# electromyography_3_channels.net
KiCad netlist of a schematic drawn in EAGLE
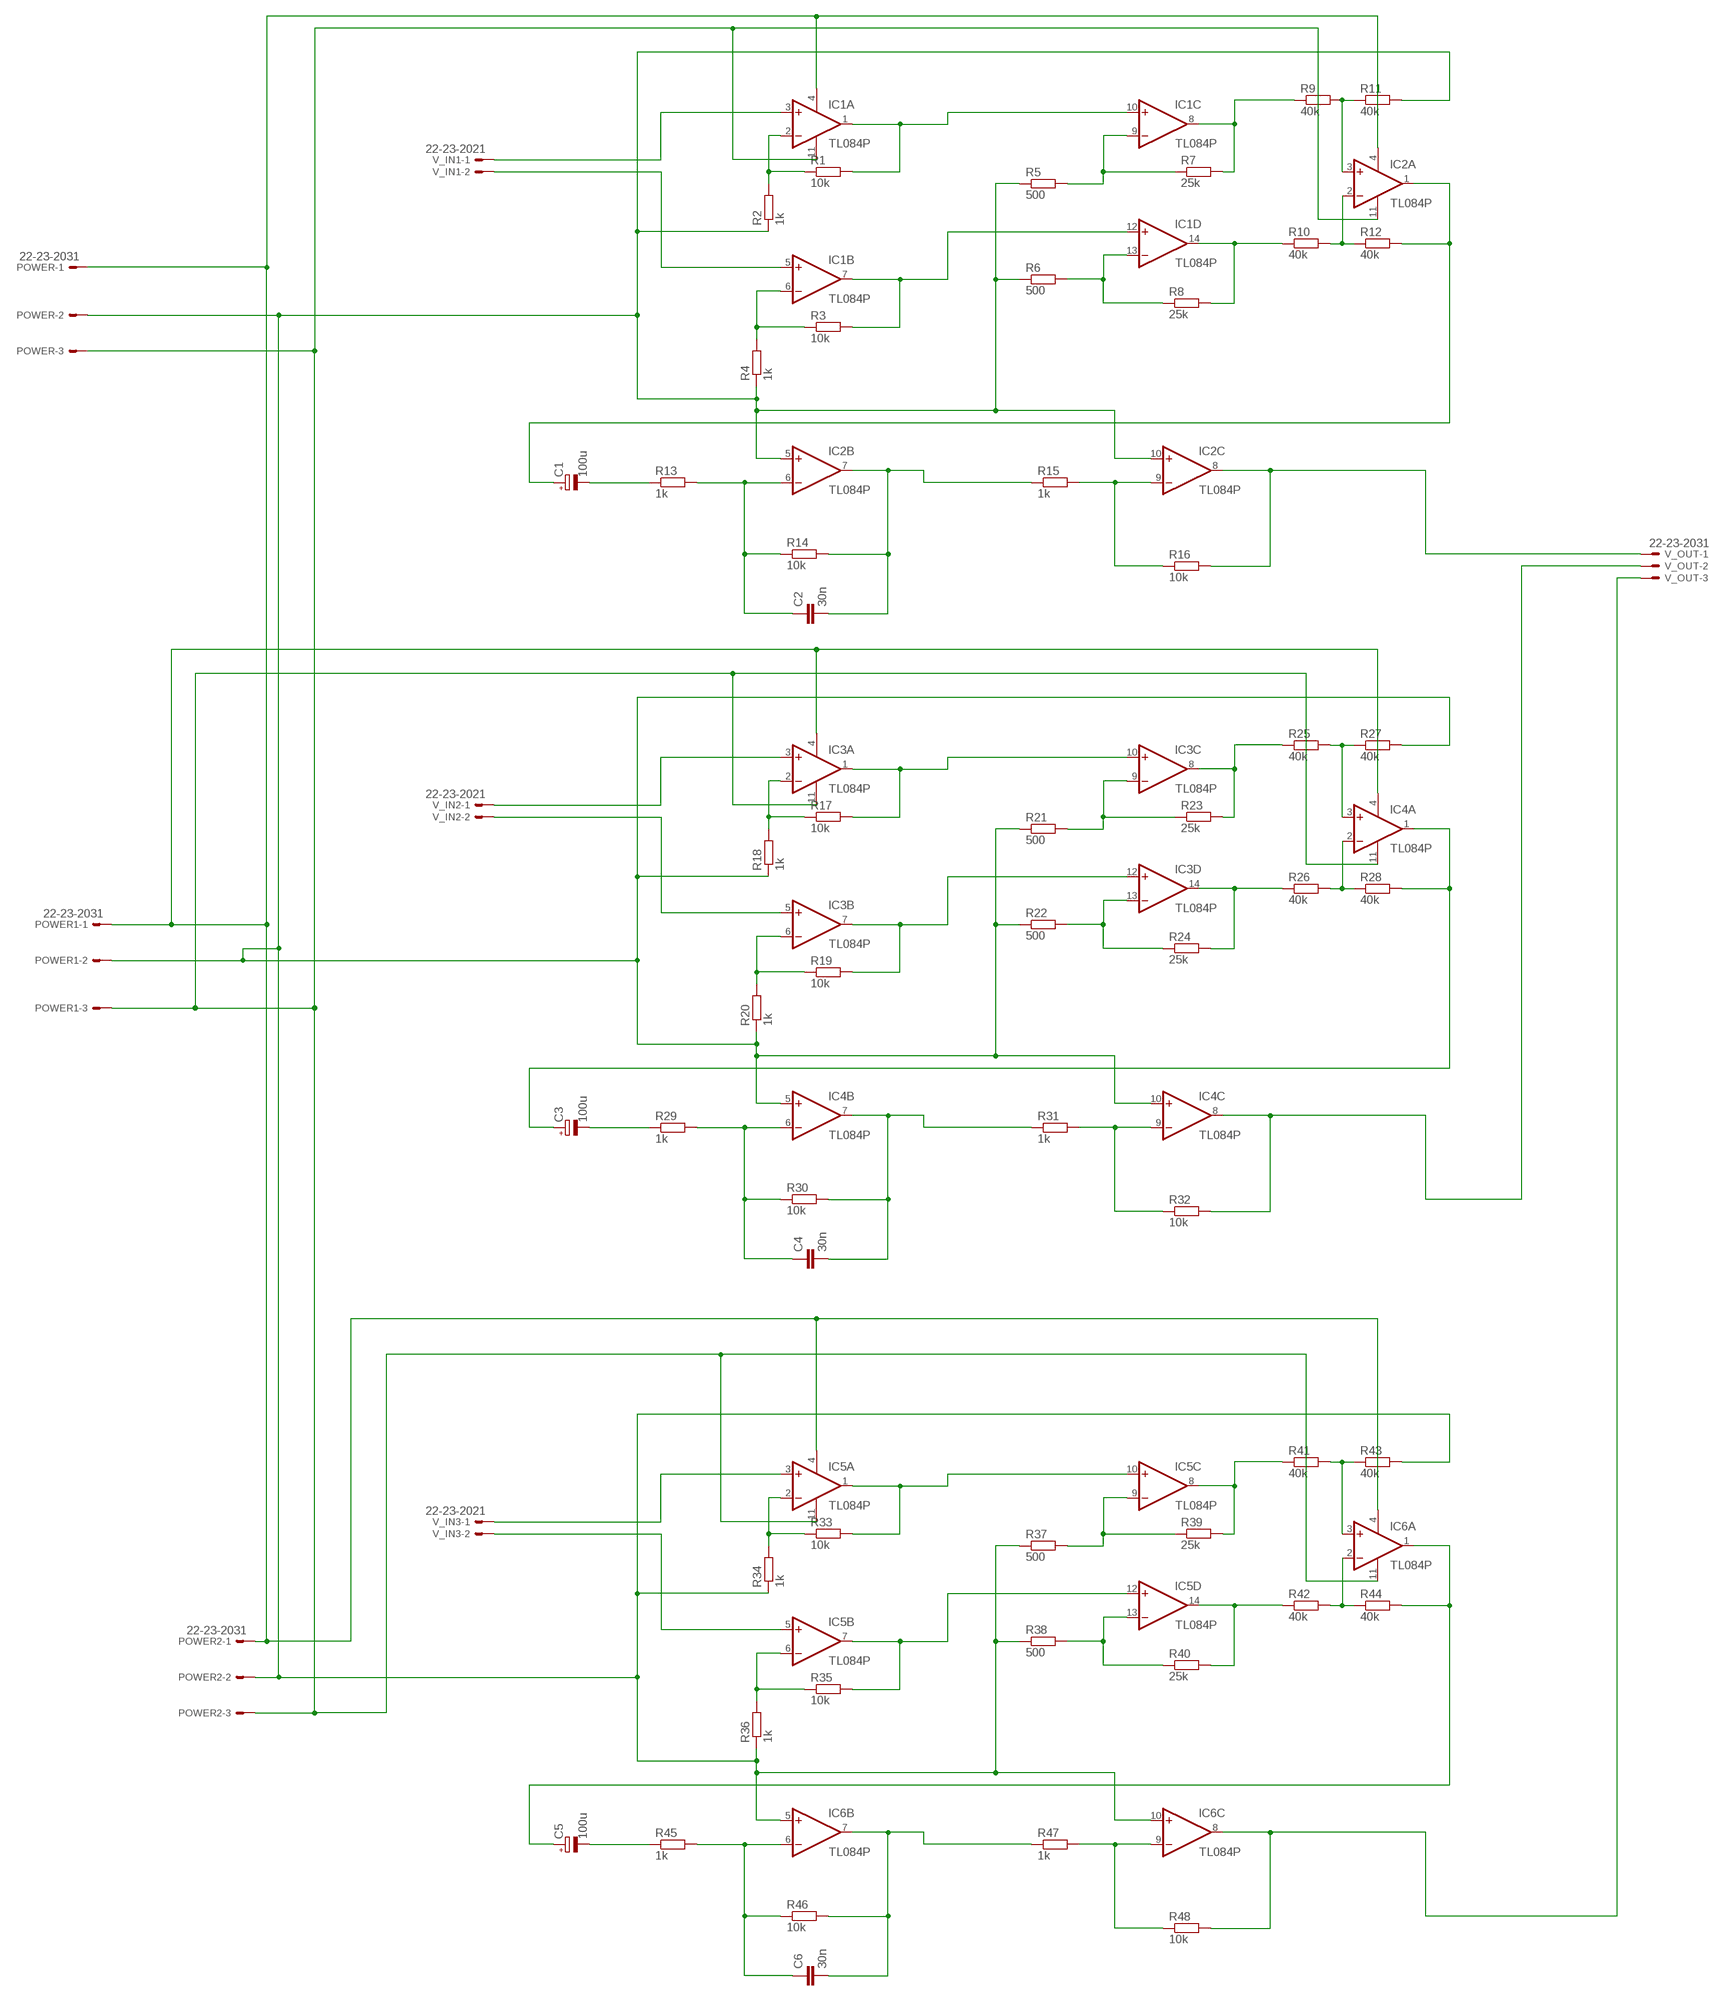
[diagram p0: schematic, sheet 1]

(export (version "E")
  (design (tool "Eeschema 10.0.6"))
  (components
    (comp (ref "C1")
      (value "100u")
      (footprint "eagle-import:E3,5-8")
      (libsource (lib "eagle-import") (part "CPOL-EUE3.5-8"))
    )
    (comp (ref "C2")
      (value "30n")
      (footprint "eagle-import:C050-024X044")
      (libsource (lib "eagle-import") (part "C-EU050-024X044"))
    )
    (comp (ref "C3")
      (value "100u")
      (footprint "eagle-import:E3,5-8")
      (libsource (lib "eagle-import") (part "CPOL-EUE3.5-8"))
    )
    (comp (ref "C4")
      (value "30n")
      (footprint "eagle-import:C050-024X044")
      (libsource (lib "eagle-import") (part "C-EU050-024X044"))
    )
    (comp (ref "C5")
      (value "100u")
      (footprint "eagle-import:E3,5-8")
      (libsource (lib "eagle-import") (part "CPOL-EUE3.5-8"))
    )
    (comp (ref "C6")
      (value "30n")
      (footprint "eagle-import:C050-024X044")
      (libsource (lib "eagle-import") (part "C-EU050-024X044"))
    )
    (comp (ref "IC1")
      (value "TL084P")
      (footprint "eagle-import:DIL14")
      (libsource (lib "eagle-import") (part "TL084P"))
    )
    (comp (ref "IC2")
      (value "TL084P")
      (footprint "eagle-import:DIL14")
      (libsource (lib "eagle-import") (part "TL084P"))
    )
    (comp (ref "IC3")
      (value "TL084P")
      (footprint "eagle-import:DIL14")
      (libsource (lib "eagle-import") (part "TL084P"))
    )
    (comp (ref "IC4")
      (value "TL084P")
      (footprint "eagle-import:DIL14")
      (libsource (lib "eagle-import") (part "TL084P"))
    )
    (comp (ref "IC5")
      (value "TL084P")
      (footprint "eagle-import:DIL14")
      (libsource (lib "eagle-import") (part "TL084P"))
    )
    (comp (ref "IC6")
      (value "TL084P")
      (footprint "eagle-import:DIL14")
      (libsource (lib "eagle-import") (part "TL084P"))
    )
    (comp (ref "POWER")
      (value "22-23-2031")
      (footprint "eagle-import:22-23-2031")
      (fields (field (name "MF") "MOLEX"))
      (libsource (lib "eagle-import") (part "22-23-2031"))
    )
    (comp (ref "POWER1")
      (value "22-23-2031")
      (footprint "eagle-import:22-23-2031")
      (fields (field (name "MF") "MOLEX"))
      (libsource (lib "eagle-import") (part "22-23-2031"))
    )
    (comp (ref "POWER2")
      (value "22-23-2031")
      (footprint "eagle-import:22-23-2031")
      (fields (field (name "MF") "MOLEX"))
      (libsource (lib "eagle-import") (part "22-23-2031"))
    )
    (comp (ref "R1")
      (value "10k")
      (footprint "eagle-import:0207_10")
      (libsource (lib "eagle-import") (part "R-EU_0207/10"))
    )
    (comp (ref "R2")
      (value "1k")
      (footprint "eagle-import:0207_10")
      (libsource (lib "eagle-import") (part "R-EU_0207/10"))
    )
    (comp (ref "R3")
      (value "10k")
      (footprint "eagle-import:0207_10")
      (libsource (lib "eagle-import") (part "R-EU_0207/10"))
    )
    (comp (ref "R4")
      (value "1k")
      (footprint "eagle-import:0207_10")
      (libsource (lib "eagle-import") (part "R-EU_0207/10"))
    )
    (comp (ref "R5")
      (value "500")
      (footprint "eagle-import:0207_10")
      (libsource (lib "eagle-import") (part "R-EU_0207/10"))
    )
    (comp (ref "R6")
      (value "500")
      (footprint "eagle-import:0207_10")
      (libsource (lib "eagle-import") (part "R-EU_0207/10"))
    )
    (comp (ref "R7")
      (value "25k")
      (footprint "eagle-import:0207_10")
      (libsource (lib "eagle-import") (part "R-EU_0207/10"))
    )
    (comp (ref "R8")
      (value "25k")
      (footprint "eagle-import:0207_10")
      (libsource (lib "eagle-import") (part "R-EU_0207/10"))
    )
    (comp (ref "R9")
      (value "40k")
      (footprint "eagle-import:0207_10")
      (libsource (lib "eagle-import") (part "R-EU_0207/10"))
    )
    (comp (ref "R10")
      (value "40k")
      (footprint "eagle-import:0207_10")
      (libsource (lib "eagle-import") (part "R-EU_0207/10"))
    )
    (comp (ref "R11")
      (value "40k")
      (footprint "eagle-import:0207_10")
      (libsource (lib "eagle-import") (part "R-EU_0207/10"))
    )
    (comp (ref "R12")
      (value "40k")
      (footprint "eagle-import:0207_10")
      (libsource (lib "eagle-import") (part "R-EU_0207/10"))
    )
    (comp (ref "R13")
      (value "1k")
      (footprint "eagle-import:0207_10")
      (libsource (lib "eagle-import") (part "R-EU_0207/10"))
    )
    (comp (ref "R14")
      (value "10k")
      (footprint "eagle-import:0207_10")
      (libsource (lib "eagle-import") (part "R-EU_0207/10"))
    )
    (comp (ref "R15")
      (value "1k")
      (footprint "eagle-import:0207_10")
      (libsource (lib "eagle-import") (part "R-EU_0207/10"))
    )
    (comp (ref "R16")
      (value "10k")
      (footprint "eagle-import:0207_10")
      (libsource (lib "eagle-import") (part "R-EU_0207/10"))
    )
    (comp (ref "R17")
      (value "10k")
      (footprint "eagle-import:0207_10")
      (libsource (lib "eagle-import") (part "R-EU_0207/10"))
    )
    (comp (ref "R18")
      (value "1k")
      (footprint "eagle-import:0207_10")
      (libsource (lib "eagle-import") (part "R-EU_0207/10"))
    )
    (comp (ref "R19")
      (value "10k")
      (footprint "eagle-import:0207_10")
      (libsource (lib "eagle-import") (part "R-EU_0207/10"))
    )
    (comp (ref "R20")
      (value "1k")
      (footprint "eagle-import:0207_10")
      (libsource (lib "eagle-import") (part "R-EU_0207/10"))
    )
    (comp (ref "R21")
      (value "500")
      (footprint "eagle-import:0207_10")
      (libsource (lib "eagle-import") (part "R-EU_0207/10"))
    )
    (comp (ref "R22")
      (value "500")
      (footprint "eagle-import:0207_10")
      (libsource (lib "eagle-import") (part "R-EU_0207/10"))
    )
    (comp (ref "R23")
      (value "25k")
      (footprint "eagle-import:0207_10")
      (libsource (lib "eagle-import") (part "R-EU_0207/10"))
    )
    (comp (ref "R24")
      (value "25k")
      (footprint "eagle-import:0207_10")
      (libsource (lib "eagle-import") (part "R-EU_0207/10"))
    )
    (comp (ref "R25")
      (value "40k")
      (footprint "eagle-import:0207_10")
      (libsource (lib "eagle-import") (part "R-EU_0207/10"))
    )
    (comp (ref "R26")
      (value "40k")
      (footprint "eagle-import:0207_10")
      (libsource (lib "eagle-import") (part "R-EU_0207/10"))
    )
    (comp (ref "R27")
      (value "40k")
      (footprint "eagle-import:0207_10")
      (libsource (lib "eagle-import") (part "R-EU_0207/10"))
    )
    (comp (ref "R28")
      (value "40k")
      (footprint "eagle-import:0207_10")
      (libsource (lib "eagle-import") (part "R-EU_0207/10"))
    )
    (comp (ref "R29")
      (value "1k")
      (footprint "eagle-import:0207_10")
      (libsource (lib "eagle-import") (part "R-EU_0207/10"))
    )
    (comp (ref "R30")
      (value "10k")
      (footprint "eagle-import:0207_10")
      (libsource (lib "eagle-import") (part "R-EU_0207/10"))
    )
    (comp (ref "R31")
      (value "1k")
      (footprint "eagle-import:0207_10")
      (libsource (lib "eagle-import") (part "R-EU_0207/10"))
    )
    (comp (ref "R32")
      (value "10k")
      (footprint "eagle-import:0207_10")
      (libsource (lib "eagle-import") (part "R-EU_0207/10"))
    )
    (comp (ref "R33")
      (value "10k")
      (footprint "eagle-import:0207_10")
      (libsource (lib "eagle-import") (part "R-EU_0207/10"))
    )
    (comp (ref "R34")
      (value "1k")
      (footprint "eagle-import:0207_10")
      (libsource (lib "eagle-import") (part "R-EU_0207/10"))
    )
    (comp (ref "R35")
      (value "10k")
      (footprint "eagle-import:0207_10")
      (libsource (lib "eagle-import") (part "R-EU_0207/10"))
    )
    (comp (ref "R36")
      (value "1k")
      (footprint "eagle-import:0207_10")
      (libsource (lib "eagle-import") (part "R-EU_0207/10"))
    )
    (comp (ref "R37")
      (value "500")
      (footprint "eagle-import:0207_10")
      (libsource (lib "eagle-import") (part "R-EU_0207/10"))
    )
    (comp (ref "R38")
      (value "500")
      (footprint "eagle-import:0207_10")
      (libsource (lib "eagle-import") (part "R-EU_0207/10"))
    )
    (comp (ref "R39")
      (value "25k")
      (footprint "eagle-import:0207_10")
      (libsource (lib "eagle-import") (part "R-EU_0207/10"))
    )
    (comp (ref "R40")
      (value "25k")
      (footprint "eagle-import:0207_10")
      (libsource (lib "eagle-import") (part "R-EU_0207/10"))
    )
    (comp (ref "R41")
      (value "40k")
      (footprint "eagle-import:0207_10")
      (libsource (lib "eagle-import") (part "R-EU_0207/10"))
    )
    (comp (ref "R42")
      (value "40k")
      (footprint "eagle-import:0207_10")
      (libsource (lib "eagle-import") (part "R-EU_0207/10"))
    )
    (comp (ref "R43")
      (value "40k")
      (footprint "eagle-import:0207_10")
      (libsource (lib "eagle-import") (part "R-EU_0207/10"))
    )
    (comp (ref "R44")
      (value "40k")
      (footprint "eagle-import:0207_10")
      (libsource (lib "eagle-import") (part "R-EU_0207/10"))
    )
    (comp (ref "R45")
      (value "1k")
      (footprint "eagle-import:0207_10")
      (libsource (lib "eagle-import") (part "R-EU_0207/10"))
    )
    (comp (ref "R46")
      (value "10k")
      (footprint "eagle-import:0207_10")
      (libsource (lib "eagle-import") (part "R-EU_0207/10"))
    )
    (comp (ref "R47")
      (value "1k")
      (footprint "eagle-import:0207_10")
      (libsource (lib "eagle-import") (part "R-EU_0207/10"))
    )
    (comp (ref "R48")
      (value "10k")
      (footprint "eagle-import:0207_10")
      (libsource (lib "eagle-import") (part "R-EU_0207/10"))
    )
    (comp (ref "V_IN1")
      (value "22-23-2021")
      (footprint "eagle-import:22-23-2021")
      (fields (field (name "MF") "MOLEX"))
      (libsource (lib "eagle-import") (part "22-23-2021"))
    )
    (comp (ref "V_IN2")
      (value "22-23-2021")
      (footprint "eagle-import:22-23-2021")
      (fields (field (name "MF") "MOLEX"))
      (libsource (lib "eagle-import") (part "22-23-2021"))
    )
    (comp (ref "V_IN3")
      (value "22-23-2021")
      (footprint "eagle-import:22-23-2021")
      (fields (field (name "MF") "MOLEX"))
      (libsource (lib "eagle-import") (part "22-23-2021"))
    )
    (comp (ref "V_OUT")
      (value "22-23-2031")
      (footprint "eagle-import:22-23-2031")
      (fields (field (name "MF") "MOLEX"))
      (libsource (lib "eagle-import") (part "22-23-2031"))
    )
  )
  (nets
    (net (code "1") (name "Net-(C1-Pad-)") (class "Default")
      (node (ref "C1") (pin "-") (pinfunction "-_-") (pintype "passive"))
      (node (ref "R13") (pin "1") (pinfunction "1_1") (pintype "passive"))
    )
    (net (code "2") (name "Net-(C3-Pad-)") (class "Default")
      (node (ref "C3") (pin "-") (pinfunction "-_-") (pintype "passive"))
      (node (ref "R29") (pin "1") (pinfunction "1_1") (pintype "passive"))
    )
    (net (code "3") (name "Net-(C5-Pad-)") (class "Default")
      (node (ref "C5") (pin "-") (pinfunction "-_-") (pintype "passive"))
      (node (ref "R45") (pin "1") (pinfunction "1_1") (pintype "passive"))
    )
    (net (code "4") (name "Net-(IC1A-+IN)") (class "Default")
      (node (ref "IC1") (pin "3") (pinfunction "+IN_3") (pintype "input"))
      (node (ref "V_IN1") (pin "1") (pinfunction "S_1") (pintype "passive"))
    )
    (net (code "5") (name "Net-(IC1A--IN)") (class "Default")
      (node (ref "IC1") (pin "2") (pinfunction "-IN_2") (pintype "input"))
      (node (ref "R1") (pin "1") (pinfunction "1_1") (pintype "passive"))
      (node (ref "R2") (pin "2") (pinfunction "2_2") (pintype "passive"))
    )
    (net (code "6") (name "Net-(IC1A-OUT)") (class "Default")
      (node (ref "IC1") (pin "1") (pinfunction "OUT_1") (pintype "output"))
      (node (ref "IC1") (pin "10") (pinfunction "+IN_10") (pintype "input"))
      (node (ref "R1") (pin "2") (pinfunction "2_2") (pintype "passive"))
    )
    (net (code "7") (name "Net-(IC1B-+IN)") (class "Default")
      (node (ref "IC1") (pin "5") (pinfunction "+IN_5") (pintype "input"))
      (node (ref "V_IN1") (pin "2") (pinfunction "S_2") (pintype "passive"))
    )
    (net (code "8") (name "Net-(IC1B--IN)") (class "Default")
      (node (ref "IC1") (pin "6") (pinfunction "-IN_6") (pintype "input"))
      (node (ref "R3") (pin "1") (pinfunction "1_1") (pintype "passive"))
      (node (ref "R4") (pin "2") (pinfunction "2_2") (pintype "passive"))
    )
    (net (code "9") (name "Net-(IC1B-OUT)") (class "Default")
      (node (ref "IC1") (pin "12") (pinfunction "+IN_12") (pintype "input"))
      (node (ref "IC1") (pin "7") (pinfunction "OUT_7") (pintype "output"))
      (node (ref "R3") (pin "2") (pinfunction "2_2") (pintype "passive"))
    )
    (net (code "10") (name "Net-(IC1C--IN)") (class "Default")
      (node (ref "IC1") (pin "9") (pinfunction "-IN_9") (pintype "input"))
      (node (ref "R5") (pin "2") (pinfunction "2_2") (pintype "passive"))
      (node (ref "R7") (pin "1") (pinfunction "1_1") (pintype "passive"))
    )
    (net (code "11") (name "Net-(IC1C-OUT)") (class "Default")
      (node (ref "IC1") (pin "8") (pinfunction "OUT_8") (pintype "output"))
      (node (ref "R7") (pin "2") (pinfunction "2_2") (pintype "passive"))
      (node (ref "R9") (pin "1") (pinfunction "1_1") (pintype "passive"))
    )
    (net (code "12") (name "Net-(IC1D--IN)") (class "Default")
      (node (ref "IC1") (pin "13") (pinfunction "-IN_13") (pintype "input"))
      (node (ref "R6") (pin "2") (pinfunction "2_2") (pintype "passive"))
      (node (ref "R8") (pin "1") (pinfunction "1_1") (pintype "passive"))
    )
    (net (code "13") (name "Net-(IC1D-OUT)") (class "Default")
      (node (ref "IC1") (pin "14") (pinfunction "OUT_14") (pintype "output"))
      (node (ref "R10") (pin "1") (pinfunction "1_1") (pintype "passive"))
      (node (ref "R8") (pin "2") (pinfunction "2_2") (pintype "passive"))
    )
    (net (code "14") (name "Net-(IC1E-V+)") (class "Default")
      (node (ref "IC1") (pin "4") (pinfunction "V+_4") (pintype "power_in"))
      (node (ref "IC2") (pin "4") (pinfunction "V+_4") (pintype "power_in"))
      (node (ref "IC3") (pin "4") (pinfunction "V+_4") (pintype "power_in"))
      (node (ref "IC4") (pin "4") (pinfunction "V+_4") (pintype "power_in"))
      (node (ref "IC5") (pin "4") (pinfunction "V+_4") (pintype "power_in"))
      (node (ref "IC6") (pin "4") (pinfunction "V+_4") (pintype "power_in"))
      (node (ref "POWER") (pin "1") (pinfunction "S_1") (pintype "passive"))
      (node (ref "POWER1") (pin "1") (pinfunction "S_1") (pintype "passive"))
      (node (ref "POWER2") (pin "1") (pinfunction "S_1") (pintype "passive"))
    )
    (net (code "15") (name "Net-(IC1E-V-)") (class "Default")
      (node (ref "IC1") (pin "11") (pinfunction "V-_11") (pintype "power_in"))
      (node (ref "IC2") (pin "11") (pinfunction "V-_11") (pintype "power_in"))
      (node (ref "IC3") (pin "11") (pinfunction "V-_11") (pintype "power_in"))
      (node (ref "IC4") (pin "11") (pinfunction "V-_11") (pintype "power_in"))
      (node (ref "IC5") (pin "11") (pinfunction "V-_11") (pintype "power_in"))
      (node (ref "IC6") (pin "11") (pinfunction "V-_11") (pintype "power_in"))
      (node (ref "POWER") (pin "3") (pinfunction "S_3") (pintype "passive"))
      (node (ref "POWER1") (pin "3") (pinfunction "S_3") (pintype "passive"))
      (node (ref "POWER2") (pin "3") (pinfunction "S_3") (pintype "passive"))
    )
    (net (code "16") (name "Net-(IC2A-+IN)") (class "Default")
      (node (ref "IC2") (pin "3") (pinfunction "+IN_3") (pintype "input"))
      (node (ref "R11") (pin "1") (pinfunction "1_1") (pintype "passive"))
      (node (ref "R9") (pin "2") (pinfunction "2_2") (pintype "passive"))
    )
    (net (code "17") (name "Net-(IC2A--IN)") (class "Default")
      (node (ref "IC2") (pin "2") (pinfunction "-IN_2") (pintype "input"))
      (node (ref "R10") (pin "2") (pinfunction "2_2") (pintype "passive"))
      (node (ref "R12") (pin "1") (pinfunction "1_1") (pintype "passive"))
    )
    (net (code "18") (name "Net-(IC2A-OUT)") (class "Default")
      (node (ref "C1") (pin "+") (pinfunction "+_+") (pintype "passive"))
      (node (ref "IC2") (pin "1") (pinfunction "OUT_1") (pintype "output"))
      (node (ref "R12") (pin "2") (pinfunction "2_2") (pintype "passive"))
    )
    (net (code "19") (name "Net-(IC2B-+IN)") (class "Default")
      (node (ref "IC2") (pin "10") (pinfunction "+IN_10") (pintype "input"))
      (node (ref "IC2") (pin "5") (pinfunction "+IN_5") (pintype "input"))
      (node (ref "IC4") (pin "10") (pinfunction "+IN_10") (pintype "input"))
      (node (ref "IC4") (pin "5") (pinfunction "+IN_5") (pintype "input"))
      (node (ref "IC6") (pin "10") (pinfunction "+IN_10") (pintype "input"))
      (node (ref "IC6") (pin "5") (pinfunction "+IN_5") (pintype "input"))
      (node (ref "POWER") (pin "2") (pinfunction "S_2") (pintype "passive"))
      (node (ref "POWER1") (pin "2") (pinfunction "S_2") (pintype "passive"))
      (node (ref "POWER2") (pin "2") (pinfunction "S_2") (pintype "passive"))
      (node (ref "R11") (pin "2") (pinfunction "2_2") (pintype "passive"))
      (node (ref "R18") (pin "1") (pinfunction "1_1") (pintype "passive"))
      (node (ref "R2") (pin "1") (pinfunction "1_1") (pintype "passive"))
      (node (ref "R20") (pin "1") (pinfunction "1_1") (pintype "passive"))
      (node (ref "R21") (pin "1") (pinfunction "1_1") (pintype "passive"))
      (node (ref "R22") (pin "1") (pinfunction "1_1") (pintype "passive"))
      (node (ref "R27") (pin "2") (pinfunction "2_2") (pintype "passive"))
      (node (ref "R34") (pin "1") (pinfunction "1_1") (pintype "passive"))
      (node (ref "R36") (pin "1") (pinfunction "1_1") (pintype "passive"))
      (node (ref "R37") (pin "1") (pinfunction "1_1") (pintype "passive"))
      (node (ref "R38") (pin "1") (pinfunction "1_1") (pintype "passive"))
      (node (ref "R4") (pin "1") (pinfunction "1_1") (pintype "passive"))
      (node (ref "R43") (pin "2") (pinfunction "2_2") (pintype "passive"))
      (node (ref "R5") (pin "1") (pinfunction "1_1") (pintype "passive"))
      (node (ref "R6") (pin "1") (pinfunction "1_1") (pintype "passive"))
    )
    (net (code "20") (name "Net-(IC2B--IN)") (class "Default")
      (node (ref "C2") (pin "1") (pinfunction "1_1") (pintype "passive"))
      (node (ref "IC2") (pin "6") (pinfunction "-IN_6") (pintype "input"))
      (node (ref "R13") (pin "2") (pinfunction "2_2") (pintype "passive"))
      (node (ref "R14") (pin "1") (pinfunction "1_1") (pintype "passive"))
    )
    (net (code "21") (name "Net-(IC2B-OUT)") (class "Default")
      (node (ref "C2") (pin "2") (pinfunction "2_2") (pintype "passive"))
      (node (ref "IC2") (pin "7") (pinfunction "OUT_7") (pintype "output"))
      (node (ref "R14") (pin "2") (pinfunction "2_2") (pintype "passive"))
      (node (ref "R15") (pin "1") (pinfunction "1_1") (pintype "passive"))
    )
    (net (code "22") (name "Net-(IC2C--IN)") (class "Default")
      (node (ref "IC2") (pin "9") (pinfunction "-IN_9") (pintype "input"))
      (node (ref "R15") (pin "2") (pinfunction "2_2") (pintype "passive"))
      (node (ref "R16") (pin "1") (pinfunction "1_1") (pintype "passive"))
    )
    (net (code "23") (name "Net-(IC2C-OUT)") (class "Default")
      (node (ref "IC2") (pin "8") (pinfunction "OUT_8") (pintype "output"))
      (node (ref "R16") (pin "2") (pinfunction "2_2") (pintype "passive"))
      (node (ref "V_OUT") (pin "1") (pinfunction "S_1") (pintype "passive"))
    )
    (net (code "24") (name "Net-(IC3A-+IN)") (class "Default")
      (node (ref "IC3") (pin "3") (pinfunction "+IN_3") (pintype "input"))
      (node (ref "V_IN2") (pin "1") (pinfunction "S_1") (pintype "passive"))
    )
    (net (code "25") (name "Net-(IC3A--IN)") (class "Default")
      (node (ref "IC3") (pin "2") (pinfunction "-IN_2") (pintype "input"))
      (node (ref "R17") (pin "1") (pinfunction "1_1") (pintype "passive"))
      (node (ref "R18") (pin "2") (pinfunction "2_2") (pintype "passive"))
    )
    (net (code "26") (name "Net-(IC3A-OUT)") (class "Default")
      (node (ref "IC3") (pin "1") (pinfunction "OUT_1") (pintype "output"))
      (node (ref "IC3") (pin "10") (pinfunction "+IN_10") (pintype "input"))
      (node (ref "R17") (pin "2") (pinfunction "2_2") (pintype "passive"))
    )
    (net (code "27") (name "Net-(IC3B-+IN)") (class "Default")
      (node (ref "IC3") (pin "5") (pinfunction "+IN_5") (pintype "input"))
      (node (ref "V_IN2") (pin "2") (pinfunction "S_2") (pintype "passive"))
    )
    (net (code "28") (name "Net-(IC3B--IN)") (class "Default")
      (node (ref "IC3") (pin "6") (pinfunction "-IN_6") (pintype "input"))
      (node (ref "R19") (pin "1") (pinfunction "1_1") (pintype "passive"))
      (node (ref "R20") (pin "2") (pinfunction "2_2") (pintype "passive"))
    )
    (net (code "29") (name "Net-(IC3B-OUT)") (class "Default")
      (node (ref "IC3") (pin "12") (pinfunction "+IN_12") (pintype "input"))
      (node (ref "IC3") (pin "7") (pinfunction "OUT_7") (pintype "output"))
      (node (ref "R19") (pin "2") (pinfunction "2_2") (pintype "passive"))
    )
    (net (code "30") (name "Net-(IC3C--IN)") (class "Default")
      (node (ref "IC3") (pin "9") (pinfunction "-IN_9") (pintype "input"))
      (node (ref "R21") (pin "2") (pinfunction "2_2") (pintype "passive"))
      (node (ref "R23") (pin "1") (pinfunction "1_1") (pintype "passive"))
    )
    (net (code "31") (name "Net-(IC3C-OUT)") (class "Default")
      (node (ref "IC3") (pin "8") (pinfunction "OUT_8") (pintype "output"))
      (node (ref "R23") (pin "2") (pinfunction "2_2") (pintype "passive"))
      (node (ref "R25") (pin "1") (pinfunction "1_1") (pintype "passive"))
    )
    (net (code "32") (name "Net-(IC3D--IN)") (class "Default")
      (node (ref "IC3") (pin "13") (pinfunction "-IN_13") (pintype "input"))
      (node (ref "R22") (pin "2") (pinfunction "2_2") (pintype "passive"))
      (node (ref "R24") (pin "1") (pinfunction "1_1") (pintype "passive"))
    )
    (net (code "33") (name "Net-(IC3D-OUT)") (class "Default")
      (node (ref "IC3") (pin "14") (pinfunction "OUT_14") (pintype "output"))
      (node (ref "R24") (pin "2") (pinfunction "2_2") (pintype "passive"))
      (node (ref "R26") (pin "1") (pinfunction "1_1") (pintype "passive"))
    )
    (net (code "34") (name "Net-(IC4A-+IN)") (class "Default")
      (node (ref "IC4") (pin "3") (pinfunction "+IN_3") (pintype "input"))
      (node (ref "R25") (pin "2") (pinfunction "2_2") (pintype "passive"))
      (node (ref "R27") (pin "1") (pinfunction "1_1") (pintype "passive"))
    )
    (net (code "35") (name "Net-(IC4A--IN)") (class "Default")
      (node (ref "IC4") (pin "2") (pinfunction "-IN_2") (pintype "input"))
      (node (ref "R26") (pin "2") (pinfunction "2_2") (pintype "passive"))
      (node (ref "R28") (pin "1") (pinfunction "1_1") (pintype "passive"))
    )
    (net (code "36") (name "Net-(IC4A-OUT)") (class "Default")
      (node (ref "C3") (pin "+") (pinfunction "+_+") (pintype "passive"))
      (node (ref "IC4") (pin "1") (pinfunction "OUT_1") (pintype "output"))
      (node (ref "R28") (pin "2") (pinfunction "2_2") (pintype "passive"))
    )
    (net (code "37") (name "Net-(IC4B--IN)") (class "Default")
      (node (ref "C4") (pin "1") (pinfunction "1_1") (pintype "passive"))
      (node (ref "IC4") (pin "6") (pinfunction "-IN_6") (pintype "input"))
      (node (ref "R29") (pin "2") (pinfunction "2_2") (pintype "passive"))
      (node (ref "R30") (pin "1") (pinfunction "1_1") (pintype "passive"))
    )
    (net (code "38") (name "Net-(IC4B-OUT)") (class "Default")
      (node (ref "C4") (pin "2") (pinfunction "2_2") (pintype "passive"))
      (node (ref "IC4") (pin "7") (pinfunction "OUT_7") (pintype "output"))
      (node (ref "R30") (pin "2") (pinfunction "2_2") (pintype "passive"))
      (node (ref "R31") (pin "1") (pinfunction "1_1") (pintype "passive"))
    )
    (net (code "39") (name "Net-(IC4C--IN)") (class "Default")
      (node (ref "IC4") (pin "9") (pinfunction "-IN_9") (pintype "input"))
      (node (ref "R31") (pin "2") (pinfunction "2_2") (pintype "passive"))
      (node (ref "R32") (pin "1") (pinfunction "1_1") (pintype "passive"))
    )
    (net (code "40") (name "Net-(IC4C-OUT)") (class "Default")
      (node (ref "IC4") (pin "8") (pinfunction "OUT_8") (pintype "output"))
      (node (ref "R32") (pin "2") (pinfunction "2_2") (pintype "passive"))
      (node (ref "V_OUT") (pin "2") (pinfunction "S_2") (pintype "passive"))
    )
    (net (code "41") (name "Net-(IC5A-+IN)") (class "Default")
      (node (ref "IC5") (pin "3") (pinfunction "+IN_3") (pintype "input"))
      (node (ref "V_IN3") (pin "1") (pinfunction "S_1") (pintype "passive"))
    )
    (net (code "42") (name "Net-(IC5A--IN)") (class "Default")
      (node (ref "IC5") (pin "2") (pinfunction "-IN_2") (pintype "input"))
      (node (ref "R33") (pin "1") (pinfunction "1_1") (pintype "passive"))
      (node (ref "R34") (pin "2") (pinfunction "2_2") (pintype "passive"))
    )
    (net (code "43") (name "Net-(IC5A-OUT)") (class "Default")
      (node (ref "IC5") (pin "1") (pinfunction "OUT_1") (pintype "output"))
      (node (ref "IC5") (pin "10") (pinfunction "+IN_10") (pintype "input"))
      (node (ref "R33") (pin "2") (pinfunction "2_2") (pintype "passive"))
    )
    (net (code "44") (name "Net-(IC5B-+IN)") (class "Default")
      (node (ref "IC5") (pin "5") (pinfunction "+IN_5") (pintype "input"))
      (node (ref "V_IN3") (pin "2") (pinfunction "S_2") (pintype "passive"))
    )
    (net (code "45") (name "Net-(IC5B--IN)") (class "Default")
      (node (ref "IC5") (pin "6") (pinfunction "-IN_6") (pintype "input"))
      (node (ref "R35") (pin "1") (pinfunction "1_1") (pintype "passive"))
      (node (ref "R36") (pin "2") (pinfunction "2_2") (pintype "passive"))
    )
    (net (code "46") (name "Net-(IC5B-OUT)") (class "Default")
      (node (ref "IC5") (pin "12") (pinfunction "+IN_12") (pintype "input"))
      (node (ref "IC5") (pin "7") (pinfunction "OUT_7") (pintype "output"))
      (node (ref "R35") (pin "2") (pinfunction "2_2") (pintype "passive"))
    )
    (net (code "47") (name "Net-(IC5C--IN)") (class "Default")
      (node (ref "IC5") (pin "9") (pinfunction "-IN_9") (pintype "input"))
      (node (ref "R37") (pin "2") (pinfunction "2_2") (pintype "passive"))
      (node (ref "R39") (pin "1") (pinfunction "1_1") (pintype "passive"))
    )
    (net (code "48") (name "Net-(IC5C-OUT)") (class "Default")
      (node (ref "IC5") (pin "8") (pinfunction "OUT_8") (pintype "output"))
      (node (ref "R39") (pin "2") (pinfunction "2_2") (pintype "passive"))
      (node (ref "R41") (pin "1") (pinfunction "1_1") (pintype "passive"))
    )
    (net (code "49") (name "Net-(IC5D--IN)") (class "Default")
      (node (ref "IC5") (pin "13") (pinfunction "-IN_13") (pintype "input"))
      (node (ref "R38") (pin "2") (pinfunction "2_2") (pintype "passive"))
      (node (ref "R40") (pin "1") (pinfunction "1_1") (pintype "passive"))
    )
    (net (code "50") (name "Net-(IC5D-OUT)") (class "Default")
      (node (ref "IC5") (pin "14") (pinfunction "OUT_14") (pintype "output"))
      (node (ref "R40") (pin "2") (pinfunction "2_2") (pintype "passive"))
      (node (ref "R42") (pin "1") (pinfunction "1_1") (pintype "passive"))
    )
    (net (code "51") (name "Net-(IC6A-+IN)") (class "Default")
      (node (ref "IC6") (pin "3") (pinfunction "+IN_3") (pintype "input"))
      (node (ref "R41") (pin "2") (pinfunction "2_2") (pintype "passive"))
      (node (ref "R43") (pin "1") (pinfunction "1_1") (pintype "passive"))
    )
    (net (code "52") (name "Net-(IC6A--IN)") (class "Default")
      (node (ref "IC6") (pin "2") (pinfunction "-IN_2") (pintype "input"))
      (node (ref "R42") (pin "2") (pinfunction "2_2") (pintype "passive"))
      (node (ref "R44") (pin "1") (pinfunction "1_1") (pintype "passive"))
    )
    (net (code "53") (name "Net-(IC6A-OUT)") (class "Default")
      (node (ref "C5") (pin "+") (pinfunction "+_+") (pintype "passive"))
      (node (ref "IC6") (pin "1") (pinfunction "OUT_1") (pintype "output"))
      (node (ref "R44") (pin "2") (pinfunction "2_2") (pintype "passive"))
    )
    (net (code "54") (name "Net-(IC6B--IN)") (class "Default")
      (node (ref "C6") (pin "1") (pinfunction "1_1") (pintype "passive"))
      (node (ref "IC6") (pin "6") (pinfunction "-IN_6") (pintype "input"))
      (node (ref "R45") (pin "2") (pinfunction "2_2") (pintype "passive"))
      (node (ref "R46") (pin "1") (pinfunction "1_1") (pintype "passive"))
    )
    (net (code "55") (name "Net-(IC6B-OUT)") (class "Default")
      (node (ref "C6") (pin "2") (pinfunction "2_2") (pintype "passive"))
      (node (ref "IC6") (pin "7") (pinfunction "OUT_7") (pintype "output"))
      (node (ref "R46") (pin "2") (pinfunction "2_2") (pintype "passive"))
      (node (ref "R47") (pin "1") (pinfunction "1_1") (pintype "passive"))
    )
    (net (code "56") (name "Net-(IC6C--IN)") (class "Default")
      (node (ref "IC6") (pin "9") (pinfunction "-IN_9") (pintype "input"))
      (node (ref "R47") (pin "2") (pinfunction "2_2") (pintype "passive"))
      (node (ref "R48") (pin "1") (pinfunction "1_1") (pintype "passive"))
    )
    (net (code "57") (name "Net-(IC6C-OUT)") (class "Default")
      (node (ref "IC6") (pin "8") (pinfunction "OUT_8") (pintype "output"))
      (node (ref "R48") (pin "2") (pinfunction "2_2") (pintype "passive"))
      (node (ref "V_OUT") (pin "3") (pinfunction "S_3") (pintype "passive"))
    )
  )
)
